# LPCB279_-_LIMIT_SWITCHES.net
KiCad netlist of a schematic drawn in Altium Designer
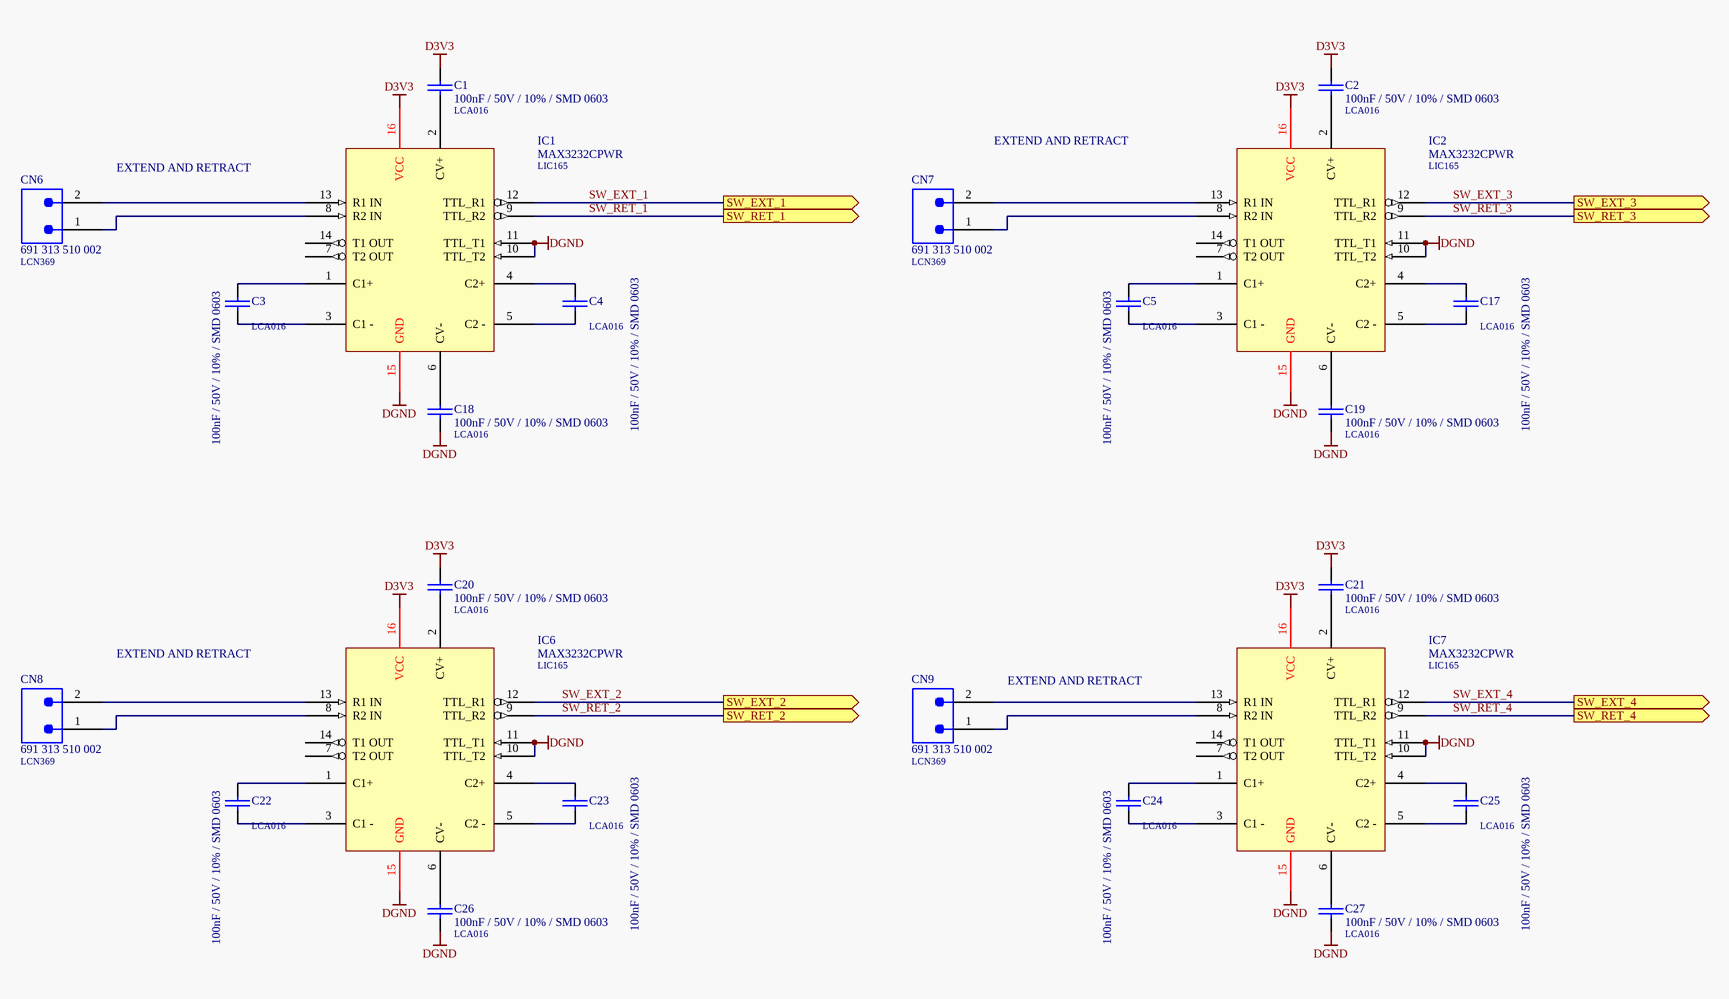
[diagram p0: LPCB279 - LIMIT SWITCHES.SchDoc]

(export (version "E")
  (design (tool "Eeschema 10.0.6"))
  (components
    (comp (ref "C1")
      (value "100nF / 50V / 10% / SMD 0603")
      (footprint "LFP011__CC1608-0603-IPC7351_B")
      (description "Capacitor, Ceramic Chip, 100nF (0.1uF), 50V, 5%, SMD 0603 [LCA016]")
      (fields (field (name "LDL_NUMBER") "LCA016"))
      (libsource (lib "LDL_Capacitors") (part "100nF / 50V / 10% / SMD 0603"))
    )
    (comp (ref "C2")
      (value "100nF / 50V / 10% / SMD 0603")
      (footprint "LFP011__CC1608-0603-IPC7351_B")
      (description "Capacitor, Ceramic Chip, 100nF (0.1uF), 50V, 5%, SMD 0603 [LCA016]")
      (fields (field (name "LDL_NUMBER") "LCA016"))
      (libsource (lib "LDL_Capacitors") (part "100nF / 50V / 10% / SMD 0603"))
    )
    (comp (ref "C3")
      (value "100nF / 50V / 10% / SMD 0603")
      (footprint "LFP011__CC1608-0603-IPC7351_B")
      (description "Capacitor, Ceramic Chip, 100nF (0.1uF), 50V, 5%, SMD 0603 [LCA016]")
      (fields (field (name "LDL_NUMBER") "LCA016"))
      (libsource (lib "LDL_Capacitors") (part "100nF / 50V / 10% / SMD 0603"))
    )
    (comp (ref "C4")
      (value "100nF / 50V / 10% / SMD 0603")
      (footprint "LFP011__CC1608-0603-IPC7351_B")
      (description "Capacitor, Ceramic Chip, 100nF (0.1uF), 50V, 5%, SMD 0603 [LCA016]")
      (fields (field (name "LDL_NUMBER") "LCA016"))
      (libsource (lib "LDL_Capacitors") (part "100nF / 50V / 10% / SMD 0603"))
    )
    (comp (ref "C5")
      (value "100nF / 50V / 10% / SMD 0603")
      (footprint "LFP011__CC1608-0603-IPC7351_B")
      (description "Capacitor, Ceramic Chip, 100nF (0.1uF), 50V, 5%, SMD 0603 [LCA016]")
      (fields (field (name "LDL_NUMBER") "LCA016"))
      (libsource (lib "LDL_Capacitors") (part "100nF / 50V / 10% / SMD 0603"))
    )
    (comp (ref "C17")
      (value "100nF / 50V / 10% / SMD 0603")
      (footprint "LFP011__CC1608-0603-IPC7351_B")
      (description "Capacitor, Ceramic Chip, 100nF (0.1uF), 50V, 5%, SMD 0603 [LCA016]")
      (fields (field (name "LDL_NUMBER") "LCA016"))
      (libsource (lib "LDL_Capacitors") (part "100nF / 50V / 10% / SMD 0603"))
    )
    (comp (ref "C18")
      (value "100nF / 50V / 10% / SMD 0603")
      (footprint "LFP011__CC1608-0603-IPC7351_B")
      (description "Capacitor, Ceramic Chip, 100nF (0.1uF), 50V, 5%, SMD 0603 [LCA016]")
      (fields (field (name "LDL_NUMBER") "LCA016"))
      (libsource (lib "LDL_Capacitors") (part "100nF / 50V / 10% / SMD 0603"))
    )
    (comp (ref "C19")
      (value "100nF / 50V / 10% / SMD 0603")
      (footprint "LFP011__CC1608-0603-IPC7351_B")
      (description "Capacitor, Ceramic Chip, 100nF (0.1uF), 50V, 5%, SMD 0603 [LCA016]")
      (fields (field (name "LDL_NUMBER") "LCA016"))
      (libsource (lib "LDL_Capacitors") (part "100nF / 50V / 10% / SMD 0603"))
    )
    (comp (ref "C20")
      (value "100nF / 50V / 10% / SMD 0603")
      (footprint "LFP011__CC1608-0603-IPC7351_B")
      (description "Capacitor, Ceramic Chip, 100nF (0.1uF), 50V, 5%, SMD 0603 [LCA016]")
      (fields (field (name "LDL_NUMBER") "LCA016"))
      (libsource (lib "LDL_Capacitors") (part "100nF / 50V / 10% / SMD 0603"))
    )
    (comp (ref "C21")
      (value "100nF / 50V / 10% / SMD 0603")
      (footprint "LFP011__CC1608-0603-IPC7351_B")
      (description "Capacitor, Ceramic Chip, 100nF (0.1uF), 50V, 5%, SMD 0603 [LCA016]")
      (fields (field (name "LDL_NUMBER") "LCA016"))
      (libsource (lib "LDL_Capacitors") (part "100nF / 50V / 10% / SMD 0603"))
    )
    (comp (ref "C22")
      (value "100nF / 50V / 10% / SMD 0603")
      (footprint "LFP011__CC1608-0603-IPC7351_B")
      (description "Capacitor, Ceramic Chip, 100nF (0.1uF), 50V, 5%, SMD 0603 [LCA016]")
      (fields (field (name "LDL_NUMBER") "LCA016"))
      (libsource (lib "LDL_Capacitors") (part "100nF / 50V / 10% / SMD 0603"))
    )
    (comp (ref "C23")
      (value "100nF / 50V / 10% / SMD 0603")
      (footprint "LFP011__CC1608-0603-IPC7351_B")
      (description "Capacitor, Ceramic Chip, 100nF (0.1uF), 50V, 5%, SMD 0603 [LCA016]")
      (fields (field (name "LDL_NUMBER") "LCA016"))
      (libsource (lib "LDL_Capacitors") (part "100nF / 50V / 10% / SMD 0603"))
    )
    (comp (ref "C24")
      (value "100nF / 50V / 10% / SMD 0603")
      (footprint "LFP011__CC1608-0603-IPC7351_B")
      (description "Capacitor, Ceramic Chip, 100nF (0.1uF), 50V, 5%, SMD 0603 [LCA016]")
      (fields (field (name "LDL_NUMBER") "LCA016"))
      (libsource (lib "LDL_Capacitors") (part "100nF / 50V / 10% / SMD 0603"))
    )
    (comp (ref "C25")
      (value "100nF / 50V / 10% / SMD 0603")
      (footprint "LFP011__CC1608-0603-IPC7351_B")
      (description "Capacitor, Ceramic Chip, 100nF (0.1uF), 50V, 5%, SMD 0603 [LCA016]")
      (fields (field (name "LDL_NUMBER") "LCA016"))
      (libsource (lib "LDL_Capacitors") (part "100nF / 50V / 10% / SMD 0603"))
    )
    (comp (ref "C26")
      (value "100nF / 50V / 10% / SMD 0603")
      (footprint "LFP011__CC1608-0603-IPC7351_B")
      (description "Capacitor, Ceramic Chip, 100nF (0.1uF), 50V, 5%, SMD 0603 [LCA016]")
      (fields (field (name "LDL_NUMBER") "LCA016"))
      (libsource (lib "LDL_Capacitors") (part "100nF / 50V / 10% / SMD 0603"))
    )
    (comp (ref "C27")
      (value "100nF / 50V / 10% / SMD 0603")
      (footprint "LFP011__CC1608-0603-IPC7351_B")
      (description "Capacitor, Ceramic Chip, 100nF (0.1uF), 50V, 5%, SMD 0603 [LCA016]")
      (fields (field (name "LDL_NUMBER") "LCA016"))
      (libsource (lib "LDL_Capacitors") (part "100nF / 50V / 10% / SMD 0603"))
    )
    (comp (ref "CN6")
      (value "691 313 510 002")
      (footprint "691 313 510 002")
      (description "Connector, Pluggable Terminal Block, 5.08mm, 2 Way, PTH")
      (fields (field (name "LDL_NUMBER") "LCN369"))
      (libsource (lib "LDL_Connectors") (part "691 313 510 002"))
    )
    (comp (ref "CN7")
      (value "691 313 510 002")
      (footprint "691 313 510 002")
      (description "Connector, Pluggable Terminal Block, 5.08mm, 2 Way, PTH")
      (fields (field (name "LDL_NUMBER") "LCN369"))
      (libsource (lib "LDL_Connectors") (part "691 313 510 002"))
    )
    (comp (ref "CN8")
      (value "691 313 510 002")
      (footprint "691 313 510 002")
      (description "Connector, Pluggable Terminal Block, 5.08mm, 2 Way, PTH")
      (fields (field (name "LDL_NUMBER") "LCN369"))
      (libsource (lib "LDL_Connectors") (part "691 313 510 002"))
    )
    (comp (ref "CN9")
      (value "691 313 510 002")
      (footprint "691 313 510 002")
      (description "Connector, Pluggable Terminal Block, 5.08mm, 2 Way, PTH")
      (fields (field (name "LDL_NUMBER") "LCN369"))
      (libsource (lib "LDL_Connectors") (part "691 313 510 002"))
    )
    (comp (ref "IC1")
      (value "MAX3232CPWR")
      (footprint "LFP049__TSSOP-16")
      (description "IC, RS232 Line Driver, 3.3V, SMD TSSOP16 [LIC165]")
      (fields (field (name "LDL_NUMBER") "LIC165"))
      (libsource (lib "LDL_Semiconductors") (part "MAX3232CPWR"))
    )
    (comp (ref "IC2")
      (value "MAX3232CPWR")
      (footprint "LFP049__TSSOP-16")
      (description "IC, RS232 Line Driver, 3.3V, SMD TSSOP16 [LIC165]")
      (fields (field (name "LDL_NUMBER") "LIC165"))
      (libsource (lib "LDL_Semiconductors") (part "MAX3232CPWR"))
    )
    (comp (ref "IC6")
      (value "MAX3232CPWR")
      (footprint "LFP049__TSSOP-16")
      (description "IC, RS232 Line Driver, 3.3V, SMD TSSOP16 [LIC165]")
      (fields (field (name "LDL_NUMBER") "LIC165"))
      (libsource (lib "LDL_Semiconductors") (part "MAX3232CPWR"))
    )
    (comp (ref "IC7")
      (value "MAX3232CPWR")
      (footprint "LFP049__TSSOP-16")
      (description "IC, RS232 Line Driver, 3.3V, SMD TSSOP16 [LIC165]")
      (fields (field (name "LDL_NUMBER") "LIC165"))
      (libsource (lib "LDL_Semiconductors") (part "MAX3232CPWR"))
    )
  )
  (nets
    (net (code "1") (name "/SW_EXT_1") (class "Default")
      (node (ref "IC1") (pin "12") (pinfunction "TTL_R1_12") (pintype "output"))
    )
    (net (code "2") (name "/SW_EXT_2") (class "Default")
      (node (ref "IC6") (pin "12") (pinfunction "TTL_R1_12") (pintype "output"))
    )
    (net (code "3") (name "/SW_EXT_3") (class "Default")
      (node (ref "IC2") (pin "12") (pinfunction "TTL_R1_12") (pintype "output"))
    )
    (net (code "4") (name "/SW_EXT_4") (class "Default")
      (node (ref "IC7") (pin "12") (pinfunction "TTL_R1_12") (pintype "output"))
    )
    (net (code "5") (name "/SW_RET_1") (class "Default")
      (node (ref "IC1") (pin "9") (pinfunction "TTL_R2_9") (pintype "output"))
    )
    (net (code "6") (name "/SW_RET_2") (class "Default")
      (node (ref "IC6") (pin "9") (pinfunction "TTL_R2_9") (pintype "output"))
    )
    (net (code "7") (name "/SW_RET_3") (class "Default")
      (node (ref "IC2") (pin "9") (pinfunction "TTL_R2_9") (pintype "output"))
    )
    (net (code "8") (name "/SW_RET_4") (class "Default")
      (node (ref "IC7") (pin "9") (pinfunction "TTL_R2_9") (pintype "output"))
    )
    (net (code "9") (name "D3V3") (class "Default")
      (node (ref "C1") (pin "1") (pintype "passive"))
      (node (ref "C2") (pin "1") (pintype "passive"))
      (node (ref "C20") (pin "1") (pintype "passive"))
      (node (ref "C21") (pin "1") (pintype "passive"))
      (node (ref "IC1") (pin "16") (pinfunction "VCC_16") (pintype "power_in"))
      (node (ref "IC2") (pin "16") (pinfunction "VCC_16") (pintype "power_in"))
      (node (ref "IC6") (pin "16") (pinfunction "VCC_16") (pintype "power_in"))
      (node (ref "IC7") (pin "16") (pinfunction "VCC_16") (pintype "power_in"))
    )
    (net (code "10") (name "DGND") (class "Default")
      (node (ref "C18") (pin "2") (pintype "passive"))
      (node (ref "C19") (pin "2") (pintype "passive"))
      (node (ref "C26") (pin "2") (pintype "passive"))
      (node (ref "C27") (pin "2") (pintype "passive"))
      (node (ref "IC1") (pin "10") (pinfunction "TTL_T2_10") (pintype "input"))
      (node (ref "IC1") (pin "11") (pinfunction "TTL_T1_11") (pintype "input"))
      (node (ref "IC1") (pin "15") (pinfunction "GND_15") (pintype "power_in"))
      (node (ref "IC2") (pin "10") (pinfunction "TTL_T2_10") (pintype "input"))
      (node (ref "IC2") (pin "11") (pinfunction "TTL_T1_11") (pintype "input"))
      (node (ref "IC2") (pin "15") (pinfunction "GND_15") (pintype "power_in"))
      (node (ref "IC6") (pin "10") (pinfunction "TTL_T2_10") (pintype "input"))
      (node (ref "IC6") (pin "11") (pinfunction "TTL_T1_11") (pintype "input"))
      (node (ref "IC6") (pin "15") (pinfunction "GND_15") (pintype "power_in"))
      (node (ref "IC7") (pin "10") (pinfunction "TTL_T2_10") (pintype "input"))
      (node (ref "IC7") (pin "11") (pinfunction "TTL_T1_11") (pintype "input"))
      (node (ref "IC7") (pin "15") (pinfunction "GND_15") (pintype "power_in"))
    )
    (net (code "11") (name "Net-(IC1-C1+)") (class "Default")
      (node (ref "C3") (pin "1") (pintype "passive"))
      (node (ref "IC1") (pin "1") (pinfunction "C1+_1") (pintype "passive"))
    )
    (net (code "12") (name "Net-(IC1-C1_-)") (class "Default")
      (node (ref "C3") (pin "2") (pintype "passive"))
      (node (ref "IC1") (pin "3") (pinfunction "C1_-_3") (pintype "passive"))
    )
    (net (code "13") (name "Net-(IC1-C2+)") (class "Default")
      (node (ref "C4") (pin "1") (pintype "passive"))
      (node (ref "IC1") (pin "4") (pinfunction "C2+_4") (pintype "passive"))
    )
    (net (code "14") (name "Net-(IC1-C2_-)") (class "Default")
      (node (ref "C4") (pin "2") (pintype "passive"))
      (node (ref "IC1") (pin "5") (pinfunction "C2_-_5") (pintype "passive"))
    )
    (net (code "15") (name "Net-(IC1-CV+)") (class "Default")
      (node (ref "C1") (pin "2") (pintype "passive"))
      (node (ref "IC1") (pin "2") (pinfunction "CV+_2") (pintype "passive"))
    )
    (net (code "16") (name "Net-(IC1-CV-)") (class "Default")
      (node (ref "C18") (pin "1") (pintype "passive"))
      (node (ref "IC1") (pin "6") (pinfunction "CV-_6") (pintype "passive"))
    )
    (net (code "17") (name "Net-(IC1-R1_IN)") (class "Default")
      (node (ref "CN6") (pin "2") (pinfunction "2_2") (pintype "passive"))
      (node (ref "IC1") (pin "13") (pinfunction "R1_IN_13") (pintype "input"))
    )
    (net (code "18") (name "Net-(IC1-R2_IN)") (class "Default")
      (node (ref "CN6") (pin "1") (pinfunction "1_1") (pintype "passive"))
      (node (ref "IC1") (pin "8") (pinfunction "R2_IN_8") (pintype "input"))
    )
    (net (code "19") (name "Net-(IC2-C1+)") (class "Default")
      (node (ref "C5") (pin "1") (pintype "passive"))
      (node (ref "IC2") (pin "1") (pinfunction "C1+_1") (pintype "passive"))
    )
    (net (code "20") (name "Net-(IC2-C1_-)") (class "Default")
      (node (ref "C5") (pin "2") (pintype "passive"))
      (node (ref "IC2") (pin "3") (pinfunction "C1_-_3") (pintype "passive"))
    )
    (net (code "21") (name "Net-(IC2-C2+)") (class "Default")
      (node (ref "C17") (pin "1") (pintype "passive"))
      (node (ref "IC2") (pin "4") (pinfunction "C2+_4") (pintype "passive"))
    )
    (net (code "22") (name "Net-(IC2-C2_-)") (class "Default")
      (node (ref "C17") (pin "2") (pintype "passive"))
      (node (ref "IC2") (pin "5") (pinfunction "C2_-_5") (pintype "passive"))
    )
    (net (code "23") (name "Net-(IC2-CV+)") (class "Default")
      (node (ref "C2") (pin "2") (pintype "passive"))
      (node (ref "IC2") (pin "2") (pinfunction "CV+_2") (pintype "passive"))
    )
    (net (code "24") (name "Net-(IC2-CV-)") (class "Default")
      (node (ref "C19") (pin "1") (pintype "passive"))
      (node (ref "IC2") (pin "6") (pinfunction "CV-_6") (pintype "passive"))
    )
    (net (code "25") (name "Net-(IC2-R1_IN)") (class "Default")
      (node (ref "CN7") (pin "2") (pinfunction "2_2") (pintype "passive"))
      (node (ref "IC2") (pin "13") (pinfunction "R1_IN_13") (pintype "input"))
    )
    (net (code "26") (name "Net-(IC2-R2_IN)") (class "Default")
      (node (ref "CN7") (pin "1") (pinfunction "1_1") (pintype "passive"))
      (node (ref "IC2") (pin "8") (pinfunction "R2_IN_8") (pintype "input"))
    )
    (net (code "27") (name "Net-(IC6-C1+)") (class "Default")
      (node (ref "C22") (pin "1") (pintype "passive"))
      (node (ref "IC6") (pin "1") (pinfunction "C1+_1") (pintype "passive"))
    )
    (net (code "28") (name "Net-(IC6-C1_-)") (class "Default")
      (node (ref "C22") (pin "2") (pintype "passive"))
      (node (ref "IC6") (pin "3") (pinfunction "C1_-_3") (pintype "passive"))
    )
    (net (code "29") (name "Net-(IC6-C2+)") (class "Default")
      (node (ref "C23") (pin "1") (pintype "passive"))
      (node (ref "IC6") (pin "4") (pinfunction "C2+_4") (pintype "passive"))
    )
    (net (code "30") (name "Net-(IC6-C2_-)") (class "Default")
      (node (ref "C23") (pin "2") (pintype "passive"))
      (node (ref "IC6") (pin "5") (pinfunction "C2_-_5") (pintype "passive"))
    )
    (net (code "31") (name "Net-(IC6-CV+)") (class "Default")
      (node (ref "C20") (pin "2") (pintype "passive"))
      (node (ref "IC6") (pin "2") (pinfunction "CV+_2") (pintype "passive"))
    )
    (net (code "32") (name "Net-(IC6-CV-)") (class "Default")
      (node (ref "C26") (pin "1") (pintype "passive"))
      (node (ref "IC6") (pin "6") (pinfunction "CV-_6") (pintype "passive"))
    )
    (net (code "33") (name "Net-(IC6-R1_IN)") (class "Default")
      (node (ref "CN8") (pin "2") (pinfunction "2_2") (pintype "passive"))
      (node (ref "IC6") (pin "13") (pinfunction "R1_IN_13") (pintype "input"))
    )
    (net (code "34") (name "Net-(IC6-R2_IN)") (class "Default")
      (node (ref "CN8") (pin "1") (pinfunction "1_1") (pintype "passive"))
      (node (ref "IC6") (pin "8") (pinfunction "R2_IN_8") (pintype "input"))
    )
    (net (code "35") (name "Net-(IC7-C1+)") (class "Default")
      (node (ref "C24") (pin "1") (pintype "passive"))
      (node (ref "IC7") (pin "1") (pinfunction "C1+_1") (pintype "passive"))
    )
    (net (code "36") (name "Net-(IC7-C1_-)") (class "Default")
      (node (ref "C24") (pin "2") (pintype "passive"))
      (node (ref "IC7") (pin "3") (pinfunction "C1_-_3") (pintype "passive"))
    )
    (net (code "37") (name "Net-(IC7-C2+)") (class "Default")
      (node (ref "C25") (pin "1") (pintype "passive"))
      (node (ref "IC7") (pin "4") (pinfunction "C2+_4") (pintype "passive"))
    )
    (net (code "38") (name "Net-(IC7-C2_-)") (class "Default")
      (node (ref "C25") (pin "2") (pintype "passive"))
      (node (ref "IC7") (pin "5") (pinfunction "C2_-_5") (pintype "passive"))
    )
    (net (code "39") (name "Net-(IC7-CV+)") (class "Default")
      (node (ref "C21") (pin "2") (pintype "passive"))
      (node (ref "IC7") (pin "2") (pinfunction "CV+_2") (pintype "passive"))
    )
    (net (code "40") (name "Net-(IC7-CV-)") (class "Default")
      (node (ref "C27") (pin "1") (pintype "passive"))
      (node (ref "IC7") (pin "6") (pinfunction "CV-_6") (pintype "passive"))
    )
    (net (code "41") (name "Net-(IC7-R1_IN)") (class "Default")
      (node (ref "CN9") (pin "2") (pinfunction "2_2") (pintype "passive"))
      (node (ref "IC7") (pin "13") (pinfunction "R1_IN_13") (pintype "input"))
    )
    (net (code "42") (name "Net-(IC7-R2_IN)") (class "Default")
      (node (ref "CN9") (pin "1") (pinfunction "1_1") (pintype "passive"))
      (node (ref "IC7") (pin "8") (pinfunction "R2_IN_8") (pintype "input"))
    )
    (net (code "43") (name "unconnected-(IC1-T1_OUT-Pad14)") (class "Default")
      (node (ref "IC1") (pin "14") (pinfunction "T1_OUT_14") (pintype "output"))
    )
    (net (code "44") (name "unconnected-(IC1-T2_OUT-Pad7)") (class "Default")
      (node (ref "IC1") (pin "7") (pinfunction "T2_OUT_7") (pintype "output"))
    )
    (net (code "45") (name "unconnected-(IC2-T1_OUT-Pad14)") (class "Default")
      (node (ref "IC2") (pin "14") (pinfunction "T1_OUT_14") (pintype "output"))
    )
    (net (code "46") (name "unconnected-(IC2-T2_OUT-Pad7)") (class "Default")
      (node (ref "IC2") (pin "7") (pinfunction "T2_OUT_7") (pintype "output"))
    )
    (net (code "47") (name "unconnected-(IC6-T1_OUT-Pad14)") (class "Default")
      (node (ref "IC6") (pin "14") (pinfunction "T1_OUT_14") (pintype "output"))
    )
    (net (code "48") (name "unconnected-(IC6-T2_OUT-Pad7)") (class "Default")
      (node (ref "IC6") (pin "7") (pinfunction "T2_OUT_7") (pintype "output"))
    )
    (net (code "49") (name "unconnected-(IC7-T1_OUT-Pad14)") (class "Default")
      (node (ref "IC7") (pin "14") (pinfunction "T1_OUT_14") (pintype "output"))
    )
    (net (code "50") (name "unconnected-(IC7-T2_OUT-Pad7)") (class "Default")
      (node (ref "IC7") (pin "7") (pinfunction "T2_OUT_7") (pintype "output"))
    )
  )
)
